# RingLight.net
KiCad netlist of a schematic drawn in EAGLE
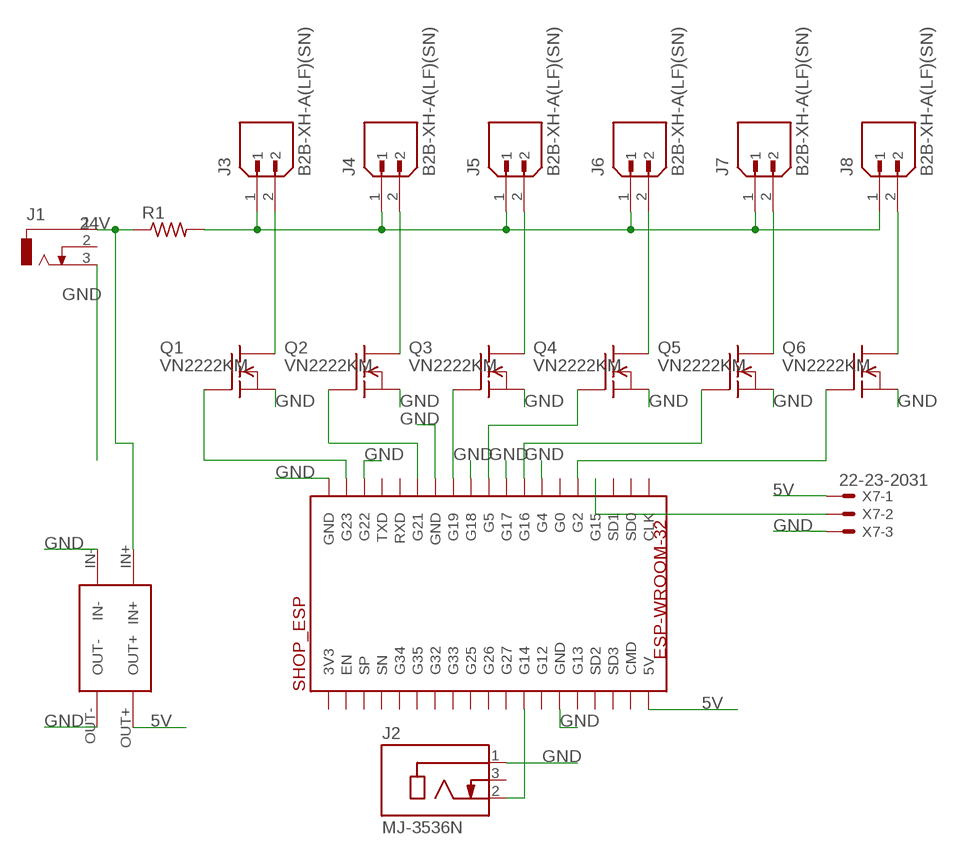
[diagram p0: schematic, sheet 1]

(export (version "E")
  (design (tool "Eeschema 10.0.6"))
  (components
    (comp (ref "J1")
      (value "DCJ0303")
      (footprint "eagle-import:DCJ0303")
      (libsource (lib "eagle-import") (part "DCJ0303"))
    )
    (comp (ref "J2")
      (value "MJ-3536N")
      (footprint "eagle-import:CUI_MJ-3536N")
      (fields (field (name "MF") "CUI Devices"))
      (libsource (lib "eagle-import") (part "MJ-3536N"))
    )
    (comp (ref "J3")
      (value "B2B-XH-A(LF)(SN)")
      (footprint "eagle-import:JST_B2B-XH-A(LF)(SN)")
      (fields (field (name "MF") "JST Sales"))
      (libsource (lib "eagle-import") (part "B2B-XH-A(LF)(SN)"))
    )
    (comp (ref "J4")
      (value "B2B-XH-A(LF)(SN)")
      (footprint "eagle-import:JST_B2B-XH-A(LF)(SN)")
      (fields (field (name "MF") "JST Sales"))
      (libsource (lib "eagle-import") (part "B2B-XH-A(LF)(SN)"))
    )
    (comp (ref "J5")
      (value "B2B-XH-A(LF)(SN)")
      (footprint "eagle-import:JST_B2B-XH-A(LF)(SN)")
      (fields (field (name "MF") "JST Sales"))
      (libsource (lib "eagle-import") (part "B2B-XH-A(LF)(SN)"))
    )
    (comp (ref "J6")
      (value "B2B-XH-A(LF)(SN)")
      (footprint "eagle-import:JST_B2B-XH-A(LF)(SN)")
      (fields (field (name "MF") "JST Sales"))
      (libsource (lib "eagle-import") (part "B2B-XH-A(LF)(SN)"))
    )
    (comp (ref "J7")
      (value "B2B-XH-A(LF)(SN)")
      (footprint "eagle-import:JST_B2B-XH-A(LF)(SN)")
      (fields (field (name "MF") "JST Sales"))
      (libsource (lib "eagle-import") (part "B2B-XH-A(LF)(SN)"))
    )
    (comp (ref "J8")
      (value "B2B-XH-A(LF)(SN)")
      (footprint "eagle-import:JST_B2B-XH-A(LF)(SN)")
      (fields (field (name "MF") "JST Sales"))
      (libsource (lib "eagle-import") (part "B2B-XH-A(LF)(SN)"))
    )
    (comp (ref "Q1")
      (value "VN2222KM")
      (footprint "eagle-import:TO237")
      (libsource (lib "eagle-import") (part "VN2222KM"))
    )
    (comp (ref "Q2")
      (value "VN2222KM")
      (footprint "eagle-import:TO237")
      (libsource (lib "eagle-import") (part "VN2222KM"))
    )
    (comp (ref "Q3")
      (value "VN2222KM")
      (footprint "eagle-import:TO237")
      (libsource (lib "eagle-import") (part "VN2222KM"))
    )
    (comp (ref "Q4")
      (value "VN2222KM")
      (footprint "eagle-import:TO237")
      (libsource (lib "eagle-import") (part "VN2222KM"))
    )
    (comp (ref "Q5")
      (value "VN2222KM")
      (footprint "eagle-import:TO237")
      (libsource (lib "eagle-import") (part "VN2222KM"))
    )
    (comp (ref "Q6")
      (value "VN2222KM")
      (footprint "eagle-import:TO237")
      (libsource (lib "eagle-import") (part "VN2222KM"))
    )
    (comp (ref "R1")
      (value "R-US_0204/7")
      (footprint "eagle-import:0204_7")
      (libsource (lib "eagle-import") (part "R-US_0204/7"))
    )
    (comp (ref "U$2")
      (value "BUCK-CONVERTER")
      (footprint "eagle-import:LM2596DC-DC")
      (libsource (lib "eagle-import") (part "BUCK-CONVERTER"))
    )
    (comp (ref "U$4")
      (value "SHOP_ESP")
      (footprint "eagle-import:ESP32-WROOM-32")
      (libsource (lib "eagle-import") (part "SHOP_ESP"))
    )
    (comp (ref "X7")
      (value "22-23-2031")
      (footprint "eagle-import:22-23-2031")
      (fields (field (name "MF") "MOLEX"))
      (libsource (lib "eagle-import") (part "22-23-2031"))
    )
  )
  (nets
    (net (code "1") (name "/3V3") (class "Default")
      (node (ref "U$4") (pin "P$19") (pinfunction "3V3_P$19") (pintype "power_in"))
    )
    (net (code "2") (name "/5V") (class "Default")
      (node (ref "U$2") (pin "OUT+") (pinfunction "OUT+_OUT+") (pintype "bidirectional"))
      (node (ref "U$4") (pin "P$1") (pinfunction "5V_P$1") (pintype "power_in"))
      (node (ref "X7") (pin "1") (pinfunction "S_1") (pintype "passive"))
    )
    (net (code "3") (name "/24V") (class "Default")
      (node (ref "J1") (pin "1") (pinfunction "1_1") (pintype "passive"))
      (node (ref "R1") (pin "1") (pinfunction "1_1") (pintype "passive"))
      (node (ref "U$2") (pin "IN+") (pinfunction "IN+_IN+") (pintype "bidirectional"))
    )
    (net (code "4") (name "/CMD") (class "Default")
      (node (ref "U$4") (pin "P$2") (pinfunction "CMD_P$2") (pintype "power_in"))
    )
    (net (code "5") (name "/GND") (class "Default")
      (node (ref "J1") (pin "3") (pinfunction "3_3") (pintype "passive"))
      (node (ref "J2") (pin "1") (pinfunction "1_1") (pintype "passive"))
      (node (ref "Q1") (pin "3") (pinfunction "S_3") (pintype "passive"))
      (node (ref "Q2") (pin "3") (pinfunction "S_3") (pintype "passive"))
      (node (ref "Q3") (pin "3") (pinfunction "S_3") (pintype "passive"))
      (node (ref "Q4") (pin "3") (pinfunction "S_3") (pintype "passive"))
      (node (ref "Q5") (pin "3") (pinfunction "S_3") (pintype "passive"))
      (node (ref "Q6") (pin "3") (pinfunction "S_3") (pintype "passive"))
      (node (ref "U$2") (pin "IN-") (pinfunction "IN-_IN-") (pintype "bidirectional"))
      (node (ref "U$2") (pin "OUT-") (pinfunction "OUT-_OUT-") (pintype "bidirectional"))
      (node (ref "U$4") (pin "P$26") (pinfunction "G4_P$26") (pintype "bidirectional"))
      (node (ref "U$4") (pin "P$28") (pinfunction "G17_P$28") (pintype "bidirectional"))
      (node (ref "U$4") (pin "P$30") (pinfunction "G18_P$30") (pintype "bidirectional"))
      (node (ref "U$4") (pin "P$32") (pinfunction "GND_P$32") (pintype "bidirectional"))
      (node (ref "U$4") (pin "P$36") (pinfunction "G22_P$36") (pintype "bidirectional"))
      (node (ref "U$4") (pin "P$38") (pinfunction "GND_P$38") (pintype "bidirectional"))
      (node (ref "U$4") (pin "P$6") (pinfunction "GND_P$6") (pintype "bidirectional"))
      (node (ref "X7") (pin "3") (pinfunction "S_3") (pintype "passive"))
    )
    (net (code "6") (name "Net-(J3-Pad1)") (class "Default")
      (node (ref "J3") (pin "1") (pinfunction "1_1") (pintype "passive"))
      (node (ref "J4") (pin "1") (pinfunction "1_1") (pintype "passive"))
      (node (ref "J5") (pin "1") (pinfunction "1_1") (pintype "passive"))
      (node (ref "J6") (pin "1") (pinfunction "1_1") (pintype "passive"))
      (node (ref "J7") (pin "1") (pinfunction "1_1") (pintype "passive"))
      (node (ref "J8") (pin "1") (pinfunction "1_1") (pintype "passive"))
      (node (ref "R1") (pin "2") (pinfunction "2_2") (pintype "passive"))
    )
    (net (code "7") (name "Net-(Q1-D)") (class "Default")
      (node (ref "J3") (pin "2") (pinfunction "2_2") (pintype "passive"))
      (node (ref "Q1") (pin "1") (pinfunction "D_1") (pintype "passive"))
    )
    (net (code "8") (name "Net-(Q1-G)") (class "Default")
      (node (ref "Q1") (pin "2") (pinfunction "G_2") (pintype "passive"))
      (node (ref "U$4") (pin "P$37") (pinfunction "G23_P$37") (pintype "bidirectional"))
    )
    (net (code "9") (name "Net-(Q2-D)") (class "Default")
      (node (ref "J4") (pin "2") (pinfunction "2_2") (pintype "passive"))
      (node (ref "Q2") (pin "1") (pinfunction "D_1") (pintype "passive"))
    )
    (net (code "10") (name "Net-(Q2-G)") (class "Default")
      (node (ref "Q2") (pin "2") (pinfunction "G_2") (pintype "passive"))
      (node (ref "U$4") (pin "P$33") (pinfunction "G21_P$33") (pintype "bidirectional"))
    )
    (net (code "11") (name "Net-(Q3-D)") (class "Default")
      (node (ref "J5") (pin "2") (pinfunction "2_2") (pintype "passive"))
      (node (ref "Q3") (pin "1") (pinfunction "D_1") (pintype "passive"))
    )
    (net (code "12") (name "Net-(Q3-G)") (class "Default")
      (node (ref "Q3") (pin "2") (pinfunction "G_2") (pintype "passive"))
      (node (ref "U$4") (pin "P$31") (pinfunction "G19_P$31") (pintype "bidirectional"))
    )
    (net (code "13") (name "Net-(Q4-D)") (class "Default")
      (node (ref "J6") (pin "2") (pinfunction "2_2") (pintype "passive"))
      (node (ref "Q4") (pin "1") (pinfunction "D_1") (pintype "passive"))
    )
    (net (code "14") (name "Net-(Q4-G)") (class "Default")
      (node (ref "Q4") (pin "2") (pinfunction "G_2") (pintype "passive"))
      (node (ref "U$4") (pin "P$29") (pinfunction "G5_P$29") (pintype "bidirectional"))
    )
    (net (code "15") (name "Net-(Q5-D)") (class "Default")
      (node (ref "J7") (pin "2") (pinfunction "2_2") (pintype "passive"))
      (node (ref "Q5") (pin "1") (pinfunction "D_1") (pintype "passive"))
    )
    (net (code "16") (name "Net-(Q5-G)") (class "Default")
      (node (ref "Q5") (pin "2") (pinfunction "G_2") (pintype "passive"))
      (node (ref "U$4") (pin "P$27") (pinfunction "G16_P$27") (pintype "bidirectional"))
    )
    (net (code "17") (name "Net-(Q6-D)") (class "Default")
      (node (ref "J8") (pin "2") (pinfunction "2_2") (pintype "passive"))
      (node (ref "Q6") (pin "1") (pinfunction "D_1") (pintype "passive"))
    )
    (net (code "18") (name "Net-(Q6-G)") (class "Default")
      (node (ref "Q6") (pin "2") (pinfunction "G_2") (pintype "passive"))
      (node (ref "U$4") (pin "P$24") (pinfunction "G2_P$24") (pintype "bidirectional"))
    )
    (net (code "19") (name "Net-(U$4-G14)") (class "Default")
      (node (ref "J2") (pin "2") (pinfunction "2_2") (pintype "passive"))
      (node (ref "U$4") (pin "P$8") (pinfunction "G14_P$8") (pintype "bidirectional"))
    )
    (net (code "20") (name "Net-(U$4-G15)") (class "Default")
      (node (ref "U$4") (pin "P$23") (pinfunction "G15_P$23") (pintype "bidirectional"))
      (node (ref "X7") (pin "2") (pinfunction "S_2") (pintype "passive"))
    )
    (net (code "21") (name "unconnected-(J1-Pad2)") (class "Default")
      (node (ref "J1") (pin "2") (pinfunction "2_2") (pintype "passive"))
    )
    (net (code "22") (name "unconnected-(J2-Pad3)") (class "Default")
      (node (ref "J2") (pin "3") (pinfunction "3_3") (pintype "passive"))
    )
    (net (code "23") (name "unconnected-(U$4-CLK-PadP$20)") (class "Default")
      (node (ref "U$4") (pin "P$20") (pinfunction "CLK_P$20") (pintype "bidirectional"))
    )
    (net (code "24") (name "unconnected-(U$4-EN-PadP$18)") (class "Default")
      (node (ref "U$4") (pin "P$18") (pinfunction "EN_P$18") (pintype "bidirectional"))
    )
    (net (code "25") (name "unconnected-(U$4-G0-PadP$25)") (class "Default")
      (node (ref "U$4") (pin "P$25") (pinfunction "G0_P$25") (pintype "bidirectional"))
    )
    (net (code "26") (name "unconnected-(U$4-G12-PadP$7)") (class "Default")
      (node (ref "U$4") (pin "P$7") (pinfunction "G12_P$7") (pintype "bidirectional"))
    )
    (net (code "27") (name "unconnected-(U$4-G13-PadP$5)") (class "Default")
      (node (ref "U$4") (pin "P$5") (pinfunction "G13_P$5") (pintype "bidirectional"))
    )
    (net (code "28") (name "unconnected-(U$4-G25-PadP$11)") (class "Default")
      (node (ref "U$4") (pin "P$11") (pinfunction "G25_P$11") (pintype "bidirectional"))
    )
    (net (code "29") (name "unconnected-(U$4-G26-PadP$10)") (class "Default")
      (node (ref "U$4") (pin "P$10") (pinfunction "G26_P$10") (pintype "bidirectional"))
    )
    (net (code "30") (name "unconnected-(U$4-G27-PadP$9)") (class "Default")
      (node (ref "U$4") (pin "P$9") (pinfunction "G27_P$9") (pintype "bidirectional"))
    )
    (net (code "31") (name "unconnected-(U$4-G32-PadP$13)") (class "Default")
      (node (ref "U$4") (pin "P$13") (pinfunction "G32_P$13") (pintype "bidirectional"))
    )
    (net (code "32") (name "unconnected-(U$4-G33-PadP$12)") (class "Default")
      (node (ref "U$4") (pin "P$12") (pinfunction "G33_P$12") (pintype "bidirectional"))
    )
    (net (code "33") (name "unconnected-(U$4-G34-PadP$15)") (class "Default")
      (node (ref "U$4") (pin "P$15") (pinfunction "G34_P$15") (pintype "bidirectional"))
    )
    (net (code "34") (name "unconnected-(U$4-G35-PadP$14)") (class "Default")
      (node (ref "U$4") (pin "P$14") (pinfunction "G35_P$14") (pintype "bidirectional"))
    )
    (net (code "35") (name "unconnected-(U$4-RXD-PadP$34)") (class "Default")
      (node (ref "U$4") (pin "P$34") (pinfunction "RXD_P$34") (pintype "bidirectional"))
    )
    (net (code "36") (name "unconnected-(U$4-SD0-PadP$21)") (class "Default")
      (node (ref "U$4") (pin "P$21") (pinfunction "SD0_P$21") (pintype "bidirectional"))
    )
    (net (code "37") (name "unconnected-(U$4-SD1-PadP$22)") (class "Default")
      (node (ref "U$4") (pin "P$22") (pinfunction "SD1_P$22") (pintype "bidirectional"))
    )
    (net (code "38") (name "unconnected-(U$4-SD2-PadP$4)") (class "Default")
      (node (ref "U$4") (pin "P$4") (pinfunction "SD2_P$4") (pintype "bidirectional"))
    )
    (net (code "39") (name "unconnected-(U$4-SD3-PadP$3)") (class "Default")
      (node (ref "U$4") (pin "P$3") (pinfunction "SD3_P$3") (pintype "bidirectional"))
    )
    (net (code "40") (name "unconnected-(U$4-SN-PadP$16)") (class "Default")
      (node (ref "U$4") (pin "P$16") (pinfunction "SN_P$16") (pintype "bidirectional"))
    )
    (net (code "41") (name "unconnected-(U$4-SP-PadP$17)") (class "Default")
      (node (ref "U$4") (pin "P$17") (pinfunction "SP_P$17") (pintype "bidirectional"))
    )
    (net (code "42") (name "unconnected-(U$4-TXD-PadP$35)") (class "Default")
      (node (ref "U$4") (pin "P$35") (pinfunction "TXD_P$35") (pintype "bidirectional"))
    )
  )
)
